# Logic_DualSupplyOD_HighGND.net
KiCad netlist of a schematic drawn in Altium Designer
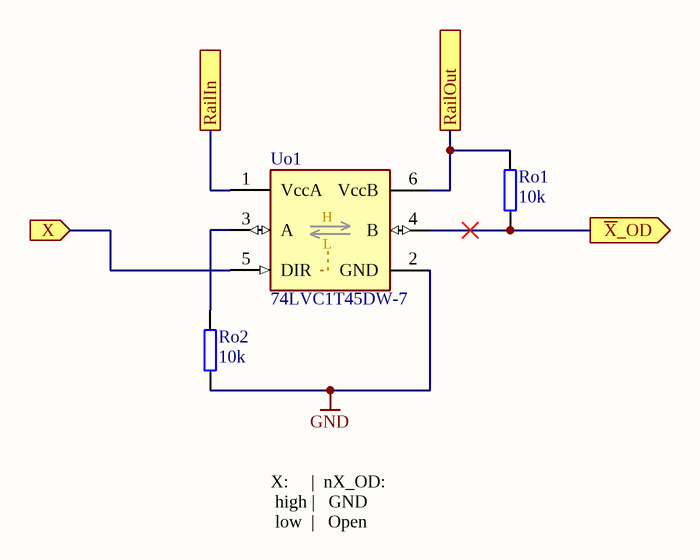
[diagram p0: Logic_DualSupplyOD_HighGND.SchDoc]

(export (version "E")
  (design (tool "Eeschema 10.0.6"))
  (components
    (comp (ref "Ro1")
      (value "10k")
      (footprint "R_0603_TE")
      (description "Generic resistor")
      (fields
        (field (name "MANUFACTURER PART NUMBER") "UZgen_R_0603_10k")
        (field (name "MANUFACTURER") "UZgen")
        (field (name "CREATED FROM") "AGeiger")
      )
      (libsource (lib "user") (part "RES"))
    )
    (comp (ref "Ro2")
      (value "10k")
      (footprint "R_0603_TE")
      (description "Generic resistor")
      (fields
        (field (name "MANUFACTURER PART NUMBER") "UZgen_R_0603_10k")
        (field (name "MANUFACTURER") "UZgen")
        (field (name "CREATED FROM") "AGeiger")
      )
      (libsource (lib "user") (part "RES"))
    )
    (comp (ref "Uo1")
      (value "74LVC1T45DW-7")
      (footprint "SOT-363")
      (description "Single-bit Dual Power Supply Translating Transceiver with 3-state Outputs")
      (fields
        (field (name "MANUFACTURER") "Diodes Incorporated")
        (field (name "LCSC PART NUMBER") "C168855")
        (field (name "CREATED FROM") "MGeier")
      )
      (libsource (lib "user") (part "74LVC1T45"))
    )
  )
  (nets
    (net (code "1") (name "/RailIn") (class "Default")
      (node (ref "Uo1") (pin "1") (pinfunction "VccA_1") (pintype "power_in"))
    )
    (net (code "2") (name "/RailOut") (class "Default")
      (node (ref "Ro1") (pin "1") (pinfunction "1_1") (pintype "passive"))
      (node (ref "Uo1") (pin "6") (pinfunction "VccB_6") (pintype "power_in"))
    )
    (net (code "3") (name "/X") (class "Default")
      (node (ref "Uo1") (pin "5") (pinfunction "DIR_5") (pintype "input"))
    )
    (net (code "4") (name "/~{X}_OD") (class "Default")
      (node (ref "Ro1") (pin "2") (pinfunction "2_2") (pintype "passive"))
      (node (ref "Uo1") (pin "4") (pinfunction "B_4") (pintype "bidirectional"))
    )
    (net (code "5") (name "GND") (class "Default")
      (node (ref "Ro2") (pin "1") (pinfunction "1_1") (pintype "passive"))
      (node (ref "Uo1") (pin "2") (pinfunction "GND_2") (pintype "power_in"))
    )
    (net (code "6") (name "Net-(Uo1-A)") (class "Default")
      (node (ref "Ro2") (pin "2") (pinfunction "2_2") (pintype "passive"))
      (node (ref "Uo1") (pin "3") (pinfunction "A_3") (pintype "bidirectional"))
    )
  )
)
